# Memory_EEPROM.net
KiCad netlist of a schematic drawn in Altium Designer
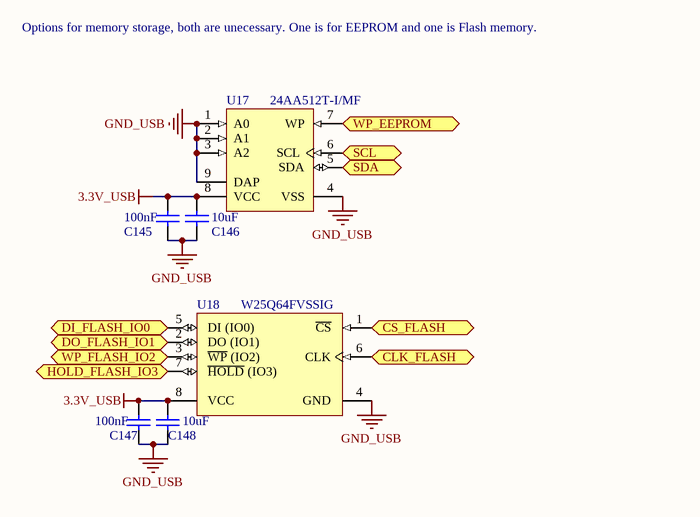
[diagram p0: Memory_EEPROM.SchDoc]

(export (version "E")
  (design (tool "Eeschema 10.0.6"))
  (components
    (comp (ref "C145")
      (value "100nF")
      (footprint "CAPC0402(1005)60_L")
      (description "0402 (1005 Metric) Chip Capacitor")
      (fields (field (name "Comment") "CAP0402"))
      (libsource (lib "Altium Content Vault") (part "CMP-1590-00004-1"))
    )
    (comp (ref "C146")
      (value "10uF")
      (footprint "CAPC0402(1005)60_L")
      (description "0402 (1005 Metric) Chip Capacitor")
      (fields (field (name "Comment") "CAP0402"))
      (libsource (lib "Altium Content Vault") (part "CMP-1590-00004-1"))
    )
    (comp (ref "C147")
      (value "100nF")
      (footprint "CAPC0402(1005)60_L")
      (description "0402 (1005 Metric) Chip Capacitor")
      (fields (field (name "Comment") "CAP0402"))
      (libsource (lib "Altium Content Vault") (part "CMP-1590-00004-1"))
    )
    (comp (ref "C148")
      (value "10uF")
      (footprint "CAPC0402(1005)60_L")
      (description "0402 (1005 Metric) Chip Capacitor")
      (fields (field (name "Comment") "CAP0402"))
      (libsource (lib "Altium Content Vault") (part "CMP-1590-00004-1"))
    )
    (comp (ref "U17")
      (value "24AA512T-I/MF")
      (footprint "DFNS-MF8")
      (description "512Kbit, 400kHz, 1.8V, I2C Serial EEPROM, 8-Pin DFN, Industrial Temperature, Tape and Reel")
      (libsource (lib "Altium Content Vault") (part "MEM-SEEPROM-34AA02-IL9"))
    )
    (comp (ref "U18")
      (value "W25Q64FVSSIG")
      (footprint "WINB-SOIC-8_M")
      (fields (field (name "MANUFACTURER") "Winbond"))
      (libsource (lib "Altium Content Vault") (part "WINB-W25Q64FVSSIG-SOIC-8"))
    )
  )
  (nets
    (net (code "1") (name "/CLK_FLASH") (class "Default")
      (node (ref "U18") (pin "6") (pinfunction "CLK_6") (pintype "input"))
    )
    (net (code "2") (name "/CS_FLASH") (class "Default")
      (node (ref "U18") (pin "1") (pinfunction "~{CS}_1") (pintype "input"))
    )
    (net (code "3") (name "/DI_FLASH_IO0") (class "Default")
      (node (ref "U18") (pin "5") (pinfunction "DI_(IO0)_5") (pintype "bidirectional"))
    )
    (net (code "4") (name "/DO_FLASH_IO1") (class "Default")
      (node (ref "U18") (pin "2") (pinfunction "DO_(IO1)_2") (pintype "bidirectional"))
    )
    (net (code "5") (name "/HOLD_FLASH_IO3") (class "Default")
      (node (ref "U18") (pin "7") (pinfunction "~{HOLD}_(IO3)_7") (pintype "bidirectional"))
    )
    (net (code "6") (name "/SCL") (class "Default")
      (node (ref "U17") (pin "6") (pinfunction "SCL_6") (pintype "input"))
    )
    (net (code "7") (name "/SDA") (class "Default")
      (node (ref "U17") (pin "5") (pinfunction "SDA_5") (pintype "bidirectional"))
    )
    (net (code "8") (name "/WP_EEPROM") (class "Default")
      (node (ref "U17") (pin "7") (pinfunction "WP_7") (pintype "input"))
    )
    (net (code "9") (name "/WP_FLASH_IO2") (class "Default")
      (node (ref "U18") (pin "3") (pinfunction "~{WP}_(IO2)_3") (pintype "bidirectional"))
    )
    (net (code "10") (name "3.3V_USB") (class "Default")
      (node (ref "C145") (pin "1") (pinfunction "1_1") (pintype "passive"))
      (node (ref "C146") (pin "1") (pinfunction "1_1") (pintype "passive"))
      (node (ref "C147") (pin "1") (pinfunction "1_1") (pintype "passive"))
      (node (ref "C148") (pin "1") (pinfunction "1_1") (pintype "passive"))
      (node (ref "U17") (pin "8") (pinfunction "VCC_8") (pintype "power_in"))
      (node (ref "U18") (pin "8") (pinfunction "VCC_8") (pintype "power_in"))
    )
    (net (code "11") (name "GND_USB") (class "Default")
      (node (ref "C145") (pin "2") (pinfunction "2_2") (pintype "passive"))
      (node (ref "C146") (pin "2") (pinfunction "2_2") (pintype "passive"))
      (node (ref "C147") (pin "2") (pinfunction "2_2") (pintype "passive"))
      (node (ref "C148") (pin "2") (pinfunction "2_2") (pintype "passive"))
      (node (ref "U17") (pin "1") (pinfunction "A0_1") (pintype "input"))
      (node (ref "U17") (pin "2") (pinfunction "A1_2") (pintype "input"))
      (node (ref "U17") (pin "3") (pinfunction "A2_3") (pintype "input"))
      (node (ref "U17") (pin "4") (pinfunction "VSS_4") (pintype "power_in"))
      (node (ref "U17") (pin "9") (pinfunction "DAP_9") (pintype "power_in"))
      (node (ref "U18") (pin "4") (pinfunction "GND_4") (pintype "power_in"))
    )
  )
)
